# Microwave.net
KiCad netlist of a schematic drawn in Altium Designer
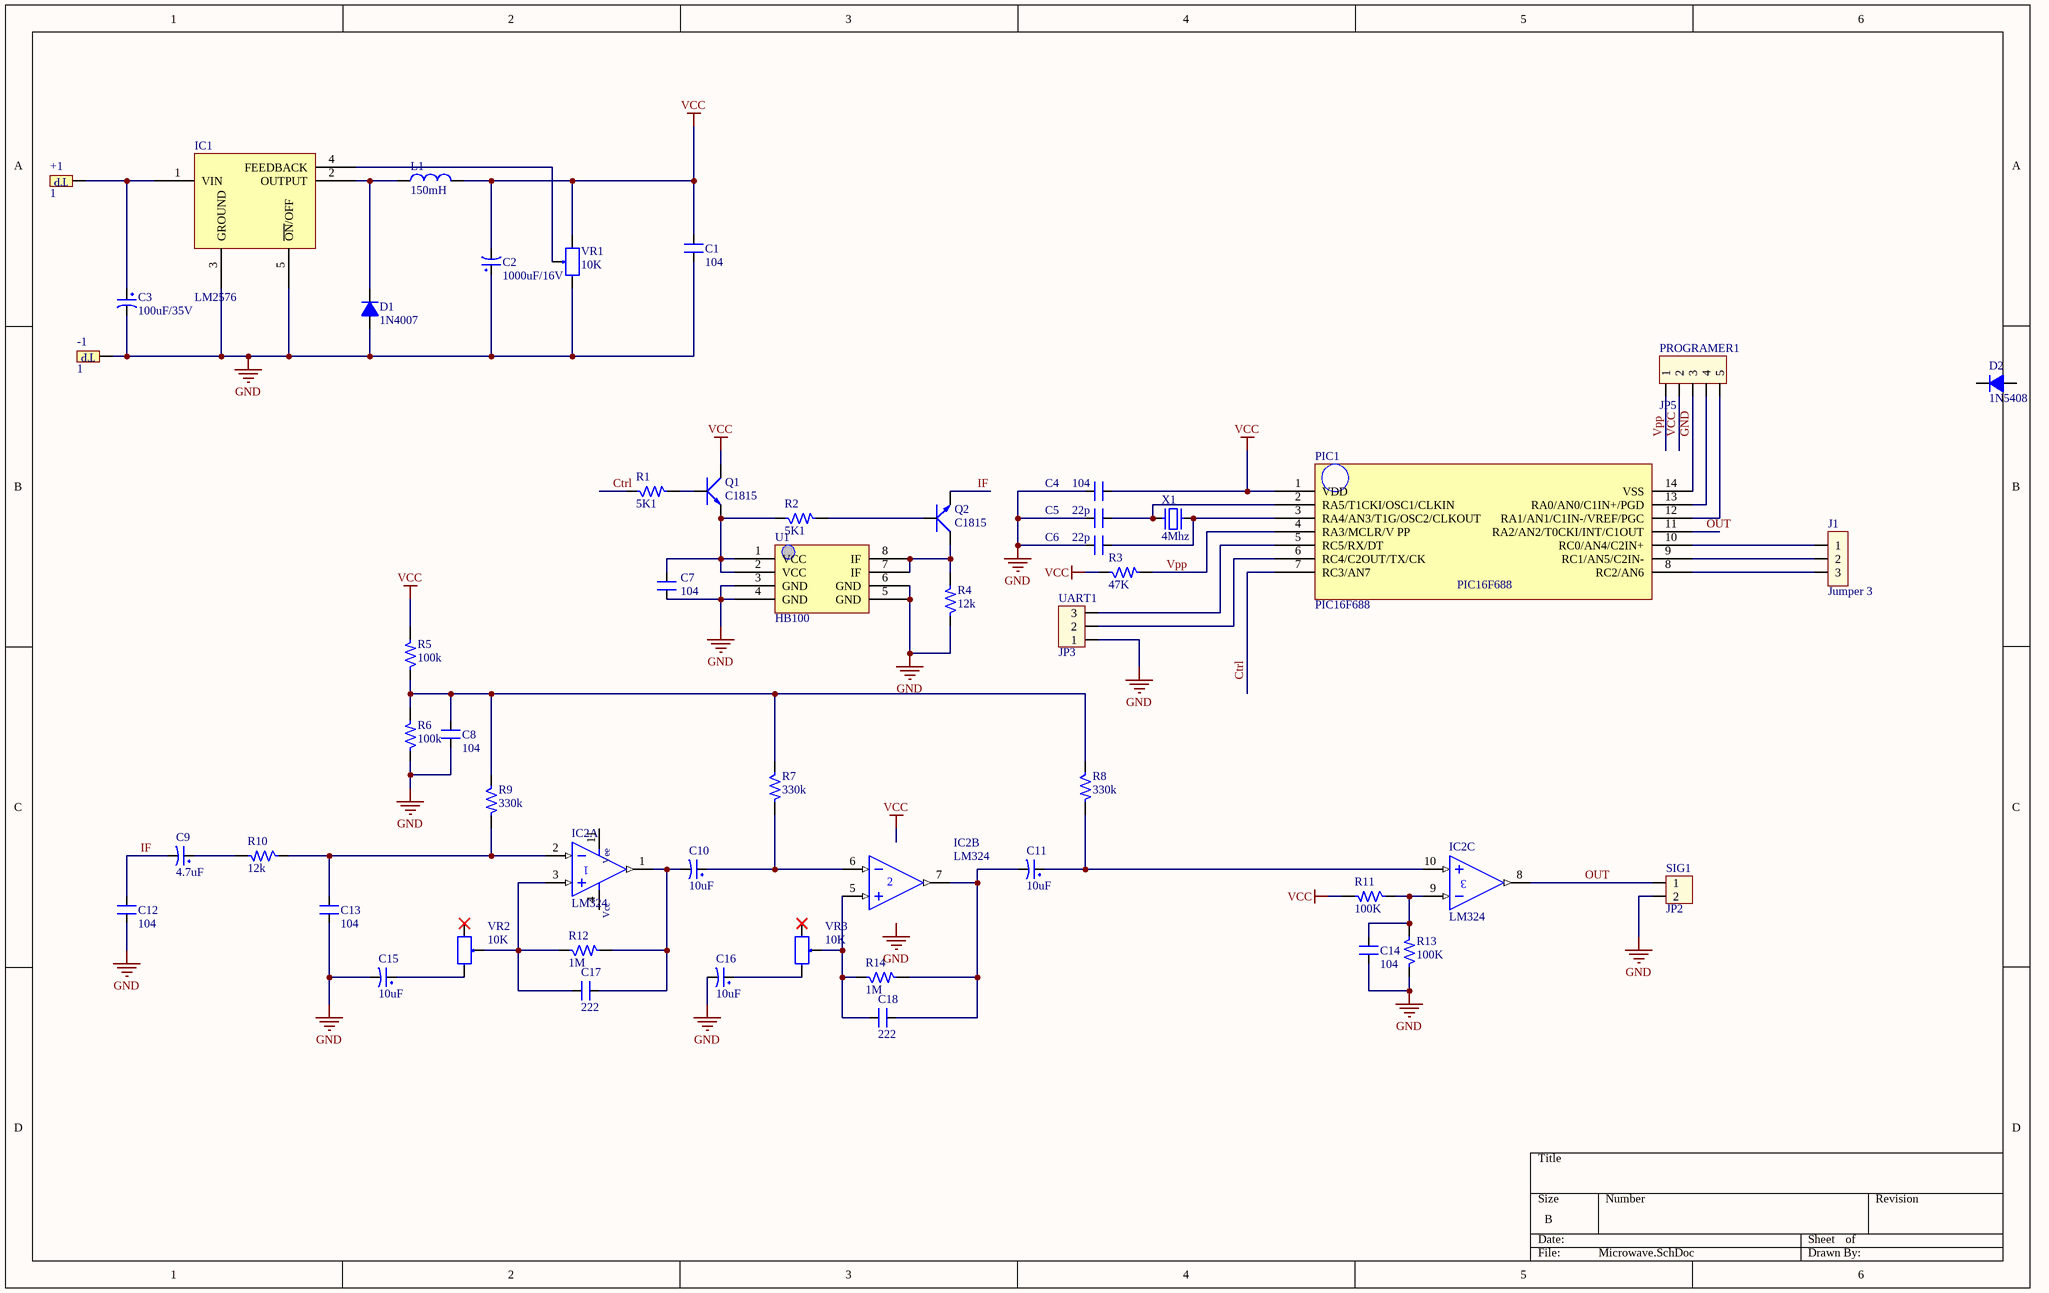
[diagram p0: Microwave.SchDoc]

(export (version "E")
  (design (tool "Eeschema 10.0.6"))
  (components
    (comp (ref "+1")
      (value "1")
      (footprint "TP")
      (description "CONNECT 1")
      (libsource (lib "syhaunguyen") (part "TP"))
    )
    (comp (ref "-1")
      (value "1")
      (footprint "TP")
      (description "CONNECT 1")
      (libsource (lib "syhaunguyen") (part "TP"))
    )
    (comp (ref "C1")
      (value "104")
      (footprint "SM-0805")
      (description "Cap np Cremic Value  104pF => 105pF")
      (libsource (lib "syhaunguyen") (part "CN2"))
    )
    (comp (ref "C2")
      (value "1000uF/16V")
      (footprint "CP1.5/3.4")
      (description "Cap 1000uF/16V - 220uF/50V")
      (libsource (lib "syhaunguyen") (part "CP4"))
    )
    (comp (ref "C3")
      (value "100uF/35V")
      (footprint "CP1.5/3.4")
      (description "Cap 100uF/35V - 470uF/16V")
      (libsource (lib "syhaunguyen") (part "CP3"))
    )
    (comp (ref "C4")
      (value "104")
      (footprint "SM-0805")
      (description "Cap SMD")
      (libsource (lib "syhaunguyen") (part "CM"))
    )
    (comp (ref "C5")
      (value "22p")
      (footprint "SM-0805")
      (description "Cap SMD")
      (libsource (lib "syhaunguyen") (part "CM"))
    )
    (comp (ref "C6")
      (value "22p")
      (footprint "SM-0805")
      (description "Cap SMD")
      (libsource (lib "syhaunguyen") (part "CM"))
    )
    (comp (ref "C7")
      (value "104")
      (footprint "SM-0805")
      (description "Cap np Cremic Value  104pF => 105pF")
      (libsource (lib "syhaunguyen") (part "CN2"))
    )
    (comp (ref "C8")
      (value "104")
      (footprint "SM-0805")
      (description "Cap np Cremic Value  104pF => 105pF")
      (libsource (lib "syhaunguyen") (part "CN2"))
    )
    (comp (ref "C9")
      (value "4.7uF")
      (footprint "CP1/2.5")
      (description "Cap P  0,1uF < 22uF , 16 - 50V")
      (libsource (lib "syhaunguyen") (part "CP1"))
    )
    (comp (ref "C10")
      (value "10uF")
      (footprint "CP1/2.5")
      (description "Cap P  0,1uF < 22uF , 16 - 50V")
      (libsource (lib "syhaunguyen") (part "CP1"))
    )
    (comp (ref "C11")
      (value "10uF")
      (footprint "CP1/2.5")
      (description "Cap P  0,1uF < 22uF , 16 - 50V")
      (libsource (lib "syhaunguyen") (part "CP1"))
    )
    (comp (ref "C12")
      (value "104")
      (footprint "SM-0805")
      (description "Cap np Cremic Value  104pF => 105pF")
      (libsource (lib "syhaunguyen") (part "CN2"))
    )
    (comp (ref "C13")
      (value "104")
      (footprint "SM-0805")
      (description "Cap np Cremic Value  104pF => 105pF")
      (libsource (lib "syhaunguyen") (part "CN2"))
    )
    (comp (ref "C14")
      (value "104")
      (footprint "SM-0805")
      (description "Cap np Cremic Value  104pF => 105pF")
      (libsource (lib "syhaunguyen") (part "CN2"))
    )
    (comp (ref "C15")
      (value "10uF")
      (footprint "CP1/2.5")
      (description "Cap P  0,1uF < 22uF , 16 - 50V")
      (libsource (lib "syhaunguyen") (part "CP1"))
    )
    (comp (ref "C16")
      (value "10uF")
      (footprint "CP1/2.5")
      (description "Cap P  0,1uF < 22uF , 16 - 50V")
      (libsource (lib "syhaunguyen") (part "CP1"))
    )
    (comp (ref "C17")
      (value "222")
      (footprint "SM-0805")
      (description "Cap np Cremic Value  104pF => 105pF")
      (libsource (lib "syhaunguyen") (part "CN2"))
    )
    (comp (ref "C18")
      (value "222")
      (footprint "SM-0805")
      (description "Cap np Cremic Value  104pF => 105pF")
      (libsource (lib "syhaunguyen") (part "CN2"))
    )
    (comp (ref "D1")
      (value "1N4007")
      (footprint "D2A")
      (description "Diode 1A")
      (libsource (lib "syhaunguyen") (part "D1A"))
    )
    (comp (ref "D2")
      (value "1N5408")
      (footprint "D5A")
      (description "Diode 5A")
      (libsource (lib "VioletofSun") (part "D5A"))
    )
    (comp (ref "IC1") (value "LM2576") (footprint "936A-02") (libsource (lib "syhaunguyen") (part "LM2576")))
    (comp (ref "IC2")
      (value "LM324")
      (footprint "SO-14")
      (description "Op x 4")
      (libsource (lib "syhaunguyen") (part "LM324"))
    )
    (comp (ref "J1") (value "Jumper 3") (footprint "JP3") (libsource (lib "syhaunguyen") (part "JP3")))
    (comp (ref "L1")
      (value "150mH")
      (footprint "L/0.4")
      (description "Inductor")
      (libsource (lib "syhaunguyen") (part "L1"))
    )
    (comp (ref "PIC1")
      (value "PIC16F688")
      (footprint "SO-14")
      (libsource (lib "syhaunguyen") (part "PIC16F688"))
    )
    (comp (ref "PROGRAMER1")
      (value "JP5")
      (footprint "CON5")
      (description "Connector 5")
      (libsource (lib "syhaunguyen") (part "Con5"))
    )
    (comp (ref "Q1")
      (value "C1815")
      (footprint "SOT23B")
      (description "NPN 600mW, ECB")
      (libsource (lib "syhaunguyen") (part "C1815"))
    )
    (comp (ref "Q2")
      (value "C1815")
      (footprint "SOT23B")
      (description "NPN 600mW, ECB")
      (libsource (lib "syhaunguyen") (part "C1815"))
    )
    (comp (ref "R1")
      (value "5K1")
      (footprint "SM-0805")
      (description "Resistor 1/4W")
      (libsource (lib "syhaunguyen") (part "R"))
    )
    (comp (ref "R2")
      (value "5K1")
      (footprint "SM-0805")
      (description "Resistor 1/4W")
      (libsource (lib "syhaunguyen") (part "R"))
    )
    (comp (ref "R3")
      (value "47K")
      (footprint "SM-0805")
      (description "Resistor 1/4W")
      (libsource (lib "syhaunguyen") (part "R"))
    )
    (comp (ref "R4")
      (value "12k")
      (footprint "SM-0805")
      (description "Resistor 1/4W")
      (libsource (lib "syhaunguyen") (part "R"))
    )
    (comp (ref "R5")
      (value "100k")
      (footprint "SM-0805")
      (description "Resistor 1/4W")
      (libsource (lib "syhaunguyen") (part "R"))
    )
    (comp (ref "R6")
      (value "100k")
      (footprint "SM-0805")
      (description "Resistor 1/4W")
      (libsource (lib "syhaunguyen") (part "R"))
    )
    (comp (ref "R7")
      (value "330k")
      (footprint "SM-0805")
      (description "Resistor 1/4W")
      (libsource (lib "syhaunguyen") (part "R"))
    )
    (comp (ref "R8")
      (value "330k")
      (footprint "SM-0805")
      (description "Resistor 1/4W")
      (libsource (lib "syhaunguyen") (part "R"))
    )
    (comp (ref "R9")
      (value "330k")
      (footprint "SM-0805")
      (description "Resistor 1/4W")
      (libsource (lib "syhaunguyen") (part "R"))
    )
    (comp (ref "R10")
      (value "12k")
      (footprint "SM-0805")
      (description "Resistor 1/4W")
      (libsource (lib "syhaunguyen") (part "R"))
    )
    (comp (ref "R11")
      (value "100K")
      (footprint "SM-0805")
      (description "Resistor 1/4W")
      (libsource (lib "syhaunguyen") (part "R"))
    )
    (comp (ref "R12")
      (value "1M")
      (footprint "SM-0805")
      (description "Resistor 1/4W")
      (libsource (lib "syhaunguyen") (part "R"))
    )
    (comp (ref "R13")
      (value "100K")
      (footprint "SM-0805")
      (description "Resistor 1/4W")
      (libsource (lib "syhaunguyen") (part "R"))
    )
    (comp (ref "R14")
      (value "1M")
      (footprint "SM-0805")
      (description "Resistor 1/4W")
      (libsource (lib "syhaunguyen") (part "R"))
    )
    (comp (ref "SIG1")
      (value "JP2")
      (footprint "CON2")
      (description "Connector 2")
      (libsource (lib "syhaunguyen") (part "Con2"))
    )
    (comp (ref "U1")
      (value "HB100")
      (footprint "HB100_SENSOR")
      (libsource (lib "syhaunguyen") (part "HB100_SENSOR"))
    )
    (comp (ref "UART1")
      (value "JP3")
      (footprint "CON3")
      (description "Connector 3")
      (libsource (lib "syhaunguyen") (part "Con3"))
    )
    (comp (ref "VR1")
      (value "10K")
      (footprint "VR1")
      (description "Var Resistor")
      (libsource (lib "syhaunguyen") (part "VR"))
    )
    (comp (ref "VR2")
      (value "10K")
      (footprint "VR")
      (description "Var Resistor")
      (libsource (lib "syhaunguyen") (part "VR"))
    )
    (comp (ref "VR3")
      (value "10K")
      (footprint "VR")
      (description "Var Resistor")
      (libsource (lib "syhaunguyen") (part "VR"))
    )
    (comp (ref "X1")
      (value "4Mhz")
      (footprint "XT2")
      (description "Crystal For all Crystal 2pin.")
      (libsource (lib "syhaunguyen") (part "XT2"))
    )
  )
  (nets
    (net (code "1") (name "/Ctrl") (class "Default")
      (node (ref "PIC1") (pin "7") (pinfunction "RC3/AN7_7") (pintype "passive"))
      (node (ref "R1") (pin "1") (pinfunction "1_1") (pintype "passive"))
    )
    (net (code "2") (name "/IF") (class "Default")
      (node (ref "C12") (pin "2") (pinfunction "2_2") (pintype "passive"))
      (node (ref "C9") (pin "2") (pinfunction "2_2") (pintype "passive"))
      (node (ref "Q2") (pin "1") (pinfunction "E_1") (pintype "passive"))
    )
    (net (code "3") (name "/OUT") (class "Default")
      (node (ref "IC2") (pin "8") (pinfunction "OUT_8") (pintype "output"))
      (node (ref "PIC1") (pin "11") (pinfunction "RA2/AN2/T0CKI/INT/C1OUT_11") (pintype "passive"))
      (node (ref "SIG1") (pin "1") (pinfunction "1_1") (pintype "passive"))
    )
    (net (code "4") (name "/Vpp") (class "Default")
      (node (ref "PIC1") (pin "4") (pinfunction "RA3/MCLR/V_PP_4") (pintype "passive"))
      (node (ref "PROGRAMER1") (pin "1") (pinfunction "1_1") (pintype "passive"))
      (node (ref "R3") (pin "2") (pinfunction "2_2") (pintype "passive"))
    )
    (net (code "5") (name "GND") (class "Default")
      (node (ref "-1") (pin "TP1") (pinfunction "0_TP1") (pintype "passive"))
      (node (ref "C1") (pin "1") (pinfunction "1_1") (pintype "passive"))
      (node (ref "C12") (pin "1") (pinfunction "1_1") (pintype "passive"))
      (node (ref "C13") (pin "1") (pinfunction "1_1") (pintype "passive"))
      (node (ref "C14") (pin "1") (pinfunction "1_1") (pintype "passive"))
      (node (ref "C15") (pin "2") (pinfunction "2_2") (pintype "passive"))
      (node (ref "C16") (pin "2") (pinfunction "2_2") (pintype "passive"))
      (node (ref "C2") (pin "1") (pinfunction "1_1") (pintype "passive"))
      (node (ref "C3") (pin "2") (pinfunction "2_2") (pintype "passive"))
      (node (ref "C4") (pin "1") (pinfunction "1_1") (pintype "passive"))
      (node (ref "C5") (pin "1") (pinfunction "1_1") (pintype "passive"))
      (node (ref "C6") (pin "1") (pinfunction "1_1") (pintype "passive"))
      (node (ref "C7") (pin "1") (pinfunction "1_1") (pintype "passive"))
      (node (ref "C8") (pin "1") (pinfunction "1_1") (pintype "passive"))
      (node (ref "D1") (pin "1") (pinfunction "A_1") (pintype "passive"))
      (node (ref "IC1") (pin "3") (pinfunction "GROUND_3") (pintype "passive"))
      (node (ref "IC1") (pin "5") (pinfunction "~{ON}/OFF_5") (pintype "passive"))
      (node (ref "PIC1") (pin "14") (pinfunction "VSS_14") (pintype "passive"))
      (node (ref "PROGRAMER1") (pin "3") (pinfunction "3_3") (pintype "passive"))
      (node (ref "R13") (pin "1") (pinfunction "1_1") (pintype "passive"))
      (node (ref "R4") (pin "1") (pinfunction "1_1") (pintype "passive"))
      (node (ref "R6") (pin "1") (pinfunction "1_1") (pintype "passive"))
      (node (ref "SIG1") (pin "2") (pinfunction "2_2") (pintype "passive"))
      (node (ref "U1") (pin "3") (pinfunction "GND_3") (pintype "passive"))
      (node (ref "U1") (pin "4") (pinfunction "GND_4") (pintype "passive"))
      (node (ref "U1") (pin "5") (pinfunction "GND_5") (pintype "passive"))
      (node (ref "U1") (pin "6") (pinfunction "GND_6") (pintype "passive"))
      (node (ref "UART1") (pin "1") (pinfunction "1_1") (pintype "passive"))
      (node (ref "VR1") (pin "3") (pinfunction "3_3") (pintype "passive"))
    )
    (net (code "6") (name "Net-(+1-0)") (class "Default")
      (node (ref "+1") (pin "TP1") (pinfunction "0_TP1") (pintype "passive"))
      (node (ref "C3") (pin "1") (pinfunction "1_1") (pintype "passive"))
      (node (ref "IC1") (pin "1") (pinfunction "VIN_1") (pintype "passive"))
    )
    (net (code "7") (name "Net-(C8-Pad2)") (class "Default")
      (node (ref "C8") (pin "2") (pinfunction "2_2") (pintype "passive"))
      (node (ref "R5") (pin "1") (pinfunction "1_1") (pintype "passive"))
      (node (ref "R6") (pin "2") (pinfunction "2_2") (pintype "passive"))
      (node (ref "R7") (pin "1") (pinfunction "1_1") (pintype "passive"))
      (node (ref "R8") (pin "1") (pinfunction "1_1") (pintype "passive"))
      (node (ref "R9") (pin "1") (pinfunction "1_1") (pintype "passive"))
    )
    (net (code "8") (name "Net-(C9-Pad1)") (class "Default")
      (node (ref "C9") (pin "1") (pinfunction "1_1") (pintype "passive"))
      (node (ref "R10") (pin "2") (pinfunction "2_2") (pintype "passive"))
    )
    (net (code "9") (name "Net-(C15-Pad1)") (class "Default")
      (node (ref "C15") (pin "1") (pinfunction "1_1") (pintype "passive"))
      (node (ref "VR2") (pin "3") (pinfunction "3_3") (pintype "passive"))
    )
    (net (code "10") (name "Net-(C16-Pad1)") (class "Default")
      (node (ref "C16") (pin "1") (pinfunction "1_1") (pintype "passive"))
      (node (ref "VR3") (pin "3") (pinfunction "3_3") (pintype "passive"))
    )
    (net (code "11") (name "Net-(D1-K)") (class "Default")
      (node (ref "D1") (pin "2") (pinfunction "K_2") (pintype "passive"))
      (node (ref "IC1") (pin "2") (pinfunction "OUTPUT_2") (pintype "passive"))
      (node (ref "L1") (pin "1") (pinfunction "1_1") (pintype "passive"))
    )
    (net (code "12") (name "Net-(IC1-FEEDBACK)") (class "Default")
      (node (ref "IC1") (pin "4") (pinfunction "FEEDBACK_4") (pintype "passive"))
      (node (ref "VR1") (pin "2") (pinfunction "2_2") (pintype "passive"))
    )
    (net (code "13") (name "Net-(IC2A-IN+)") (class "Default")
      (node (ref "C17") (pin "1") (pinfunction "1_1") (pintype "passive"))
      (node (ref "IC2") (pin "3") (pinfunction "IN+_3") (pintype "input"))
      (node (ref "R12") (pin "1") (pinfunction "1_1") (pintype "passive"))
      (node (ref "VR2") (pin "2") (pinfunction "2_2") (pintype "passive"))
    )
    (net (code "14") (name "Net-(IC2A-IN-)") (class "Default")
      (node (ref "C13") (pin "2") (pinfunction "2_2") (pintype "passive"))
      (node (ref "IC2") (pin "2") (pinfunction "IN-_2") (pintype "input"))
      (node (ref "R10") (pin "1") (pinfunction "1_1") (pintype "passive"))
      (node (ref "R9") (pin "2") (pinfunction "2_2") (pintype "passive"))
    )
    (net (code "15") (name "Net-(IC2A-OUT)") (class "Default")
      (node (ref "C10") (pin "2") (pinfunction "2_2") (pintype "passive"))
      (node (ref "C17") (pin "2") (pinfunction "2_2") (pintype "passive"))
      (node (ref "IC2") (pin "1") (pinfunction "OUT_1") (pintype "output"))
      (node (ref "R12") (pin "2") (pinfunction "2_2") (pintype "passive"))
    )
    (net (code "16") (name "Net-(IC2B-IN+)") (class "Default")
      (node (ref "C18") (pin "1") (pinfunction "1_1") (pintype "passive"))
      (node (ref "IC2") (pin "5") (pinfunction "IN+_5") (pintype "input"))
      (node (ref "R14") (pin "1") (pinfunction "1_1") (pintype "passive"))
      (node (ref "VR3") (pin "2") (pinfunction "2_2") (pintype "passive"))
    )
    (net (code "17") (name "Net-(IC2B-IN-)") (class "Default")
      (node (ref "C10") (pin "1") (pinfunction "1_1") (pintype "passive"))
      (node (ref "IC2") (pin "6") (pinfunction "IN-_6") (pintype "input"))
      (node (ref "R7") (pin "2") (pinfunction "2_2") (pintype "passive"))
    )
    (net (code "18") (name "Net-(IC2B-OUT)") (class "Default")
      (node (ref "C11") (pin "2") (pinfunction "2_2") (pintype "passive"))
      (node (ref "C18") (pin "2") (pinfunction "2_2") (pintype "passive"))
      (node (ref "IC2") (pin "7") (pinfunction "OUT_7") (pintype "output"))
      (node (ref "R14") (pin "2") (pinfunction "2_2") (pintype "passive"))
    )
    (net (code "19") (name "Net-(IC2C-IN+)") (class "Default")
      (node (ref "C11") (pin "1") (pinfunction "1_1") (pintype "passive"))
      (node (ref "IC2") (pin "10") (pinfunction "IN+_10") (pintype "input"))
      (node (ref "R8") (pin "2") (pinfunction "2_2") (pintype "passive"))
    )
    (net (code "20") (name "Net-(IC2C-IN-)") (class "Default")
      (node (ref "C14") (pin "2") (pinfunction "2_2") (pintype "passive"))
      (node (ref "IC2") (pin "9") (pinfunction "IN-_9") (pintype "input"))
      (node (ref "R11") (pin "1") (pinfunction "1_1") (pintype "passive"))
      (node (ref "R13") (pin "2") (pinfunction "2_2") (pintype "passive"))
    )
    (net (code "21") (name "Net-(PIC1-RA0{slash}AN0{slash}C1IN+{slash}PGD)") (class "Default")
      (node (ref "PIC1") (pin "13") (pinfunction "RA0/AN0/C1IN+/PGD_13") (pintype "passive"))
      (node (ref "PROGRAMER1") (pin "4") (pinfunction "4_4") (pintype "passive"))
    )
    (net (code "22") (name "Net-(PIC1-RA1{slash}AN1{slash}C1IN-{slash}VREF{slash}PGC)") (class "Default")
      (node (ref "PIC1") (pin "12") (pinfunction "RA1/AN1/C1IN-/VREF/PGC_12") (pintype "passive"))
      (node (ref "PROGRAMER1") (pin "5") (pinfunction "5_5") (pintype "passive"))
    )
    (net (code "23") (name "Net-(PIC1-RA4{slash}AN3{slash}T1G{slash}OSC2{slash}CLKOUT)") (class "Default")
      (node (ref "C6") (pin "2") (pinfunction "2_2") (pintype "passive"))
      (node (ref "PIC1") (pin "3") (pinfunction "RA4/AN3/T1G/OSC2/CLKOUT_3") (pintype "passive"))
      (node (ref "X1") (pin "2") (pinfunction "2_2") (pintype "passive"))
    )
    (net (code "24") (name "Net-(PIC1-RA5{slash}T1CKI{slash}OSC1{slash}CLKIN)") (class "Default")
      (node (ref "C5") (pin "2") (pinfunction "2_2") (pintype "passive"))
      (node (ref "PIC1") (pin "2") (pinfunction "RA5/T1CKI/OSC1/CLKIN_2") (pintype "passive"))
      (node (ref "X1") (pin "1") (pinfunction "1_1") (pintype "passive"))
    )
    (net (code "25") (name "Net-(PIC1-RC0{slash}AN4{slash}C2IN+)") (class "Default")
      (node (ref "J1") (pin "1") (pinfunction "1_1") (pintype "passive"))
      (node (ref "PIC1") (pin "10") (pinfunction "RC0/AN4/C2IN+_10") (pintype "passive"))
    )
    (net (code "26") (name "Net-(PIC1-RC1{slash}AN5{slash}C2IN-)") (class "Default")
      (node (ref "J1") (pin "2") (pinfunction "2_2") (pintype "passive"))
      (node (ref "PIC1") (pin "9") (pinfunction "RC1/AN5/C2IN-_9") (pintype "passive"))
    )
    (net (code "27") (name "Net-(PIC1-RC2{slash}AN6)") (class "Default")
      (node (ref "J1") (pin "3") (pinfunction "3_3") (pintype "passive"))
      (node (ref "PIC1") (pin "8") (pinfunction "RC2/AN6_8") (pintype "passive"))
    )
    (net (code "28") (name "Net-(PIC1-RC4{slash}C2OUT{slash}TX{slash}CK)") (class "Default")
      (node (ref "PIC1") (pin "6") (pinfunction "RC4/C2OUT/TX/CK_6") (pintype "passive"))
      (node (ref "UART1") (pin "2") (pinfunction "2_2") (pintype "passive"))
    )
    (net (code "29") (name "Net-(PIC1-RC5{slash}RX{slash}DT)") (class "Default")
      (node (ref "PIC1") (pin "5") (pinfunction "RC5/RX/DT_5") (pintype "passive"))
      (node (ref "UART1") (pin "3") (pinfunction "3_3") (pintype "passive"))
    )
    (net (code "30") (name "Net-(Q1-B)") (class "Default")
      (node (ref "Q1") (pin "3") (pinfunction "B_3") (pintype "passive"))
      (node (ref "R1") (pin "2") (pinfunction "2_2") (pintype "passive"))
    )
    (net (code "31") (name "Net-(Q1-E)") (class "Default")
      (node (ref "C7") (pin "2") (pinfunction "2_2") (pintype "passive"))
      (node (ref "Q1") (pin "1") (pinfunction "E_1") (pintype "passive"))
      (node (ref "R2") (pin "1") (pinfunction "1_1") (pintype "passive"))
      (node (ref "U1") (pin "1") (pinfunction "VCC_1") (pintype "passive"))
      (node (ref "U1") (pin "2") (pinfunction "VCC_2") (pintype "passive"))
    )
    (net (code "32") (name "Net-(Q2-B)") (class "Default")
      (node (ref "Q2") (pin "3") (pinfunction "B_3") (pintype "passive"))
      (node (ref "R2") (pin "2") (pinfunction "2_2") (pintype "passive"))
    )
    (net (code "33") (name "Net-(Q2-C)") (class "Default")
      (node (ref "Q2") (pin "2") (pinfunction "C_2") (pintype "passive"))
      (node (ref "R4") (pin "2") (pinfunction "2_2") (pintype "passive"))
      (node (ref "U1") (pin "7") (pinfunction "IF_7") (pintype "passive"))
      (node (ref "U1") (pin "8") (pinfunction "IF_8") (pintype "passive"))
    )
    (net (code "34") (name "VCC") (class "Default")
      (node (ref "C1") (pin "2") (pinfunction "2_2") (pintype "passive"))
      (node (ref "C2") (pin "2") (pinfunction "2_2") (pintype "passive"))
      (node (ref "C4") (pin "2") (pinfunction "2_2") (pintype "passive"))
      (node (ref "L1") (pin "2") (pinfunction "2_2") (pintype "passive"))
      (node (ref "PIC1") (pin "1") (pinfunction "VDD_1") (pintype "passive"))
      (node (ref "PROGRAMER1") (pin "2") (pinfunction "2_2") (pintype "passive"))
      (node (ref "Q1") (pin "2") (pinfunction "C_2") (pintype "passive"))
      (node (ref "R11") (pin "2") (pinfunction "2_2") (pintype "passive"))
      (node (ref "R3") (pin "1") (pinfunction "1_1") (pintype "passive"))
      (node (ref "R5") (pin "2") (pinfunction "2_2") (pintype "passive"))
      (node (ref "VR1") (pin "1") (pinfunction "1_1") (pintype "passive"))
    )
    (net (code "35") (name "unconnected-(D2-A-Pad1)") (class "Default")
      (node (ref "D2") (pin "1") (pinfunction "A_1") (pintype "passive"))
    )
    (net (code "36") (name "unconnected-(D2-K-Pad2)") (class "Default")
      (node (ref "D2") (pin "2") (pinfunction "K_2") (pintype "passive"))
    )
    (net (code "37") (name "unconnected-(IC2A-V+-Pad4)") (class "Default")
      (node (ref "IC2") (pin "4") (pinfunction "V+_4") (pintype "power_in"))
    )
    (net (code "38") (name "unconnected-(IC2A-V--Pad11)") (class "Default")
      (node (ref "IC2") (pin "11") (pinfunction "V-_11") (pintype "power_in"))
    )
    (net (code "39") (name "unconnected-(VR2-Pad1)") (class "Default")
      (node (ref "VR2") (pin "1") (pinfunction "1_1") (pintype "passive+no_connect"))
    )
    (net (code "40") (name "unconnected-(VR3-Pad1)") (class "Default")
      (node (ref "VR3") (pin "1") (pinfunction "1_1") (pintype "passive+no_connect"))
    )
  )
)
